# Arduino_PyunPyun.net
KiCad netlist of a schematic drawn in EAGLE
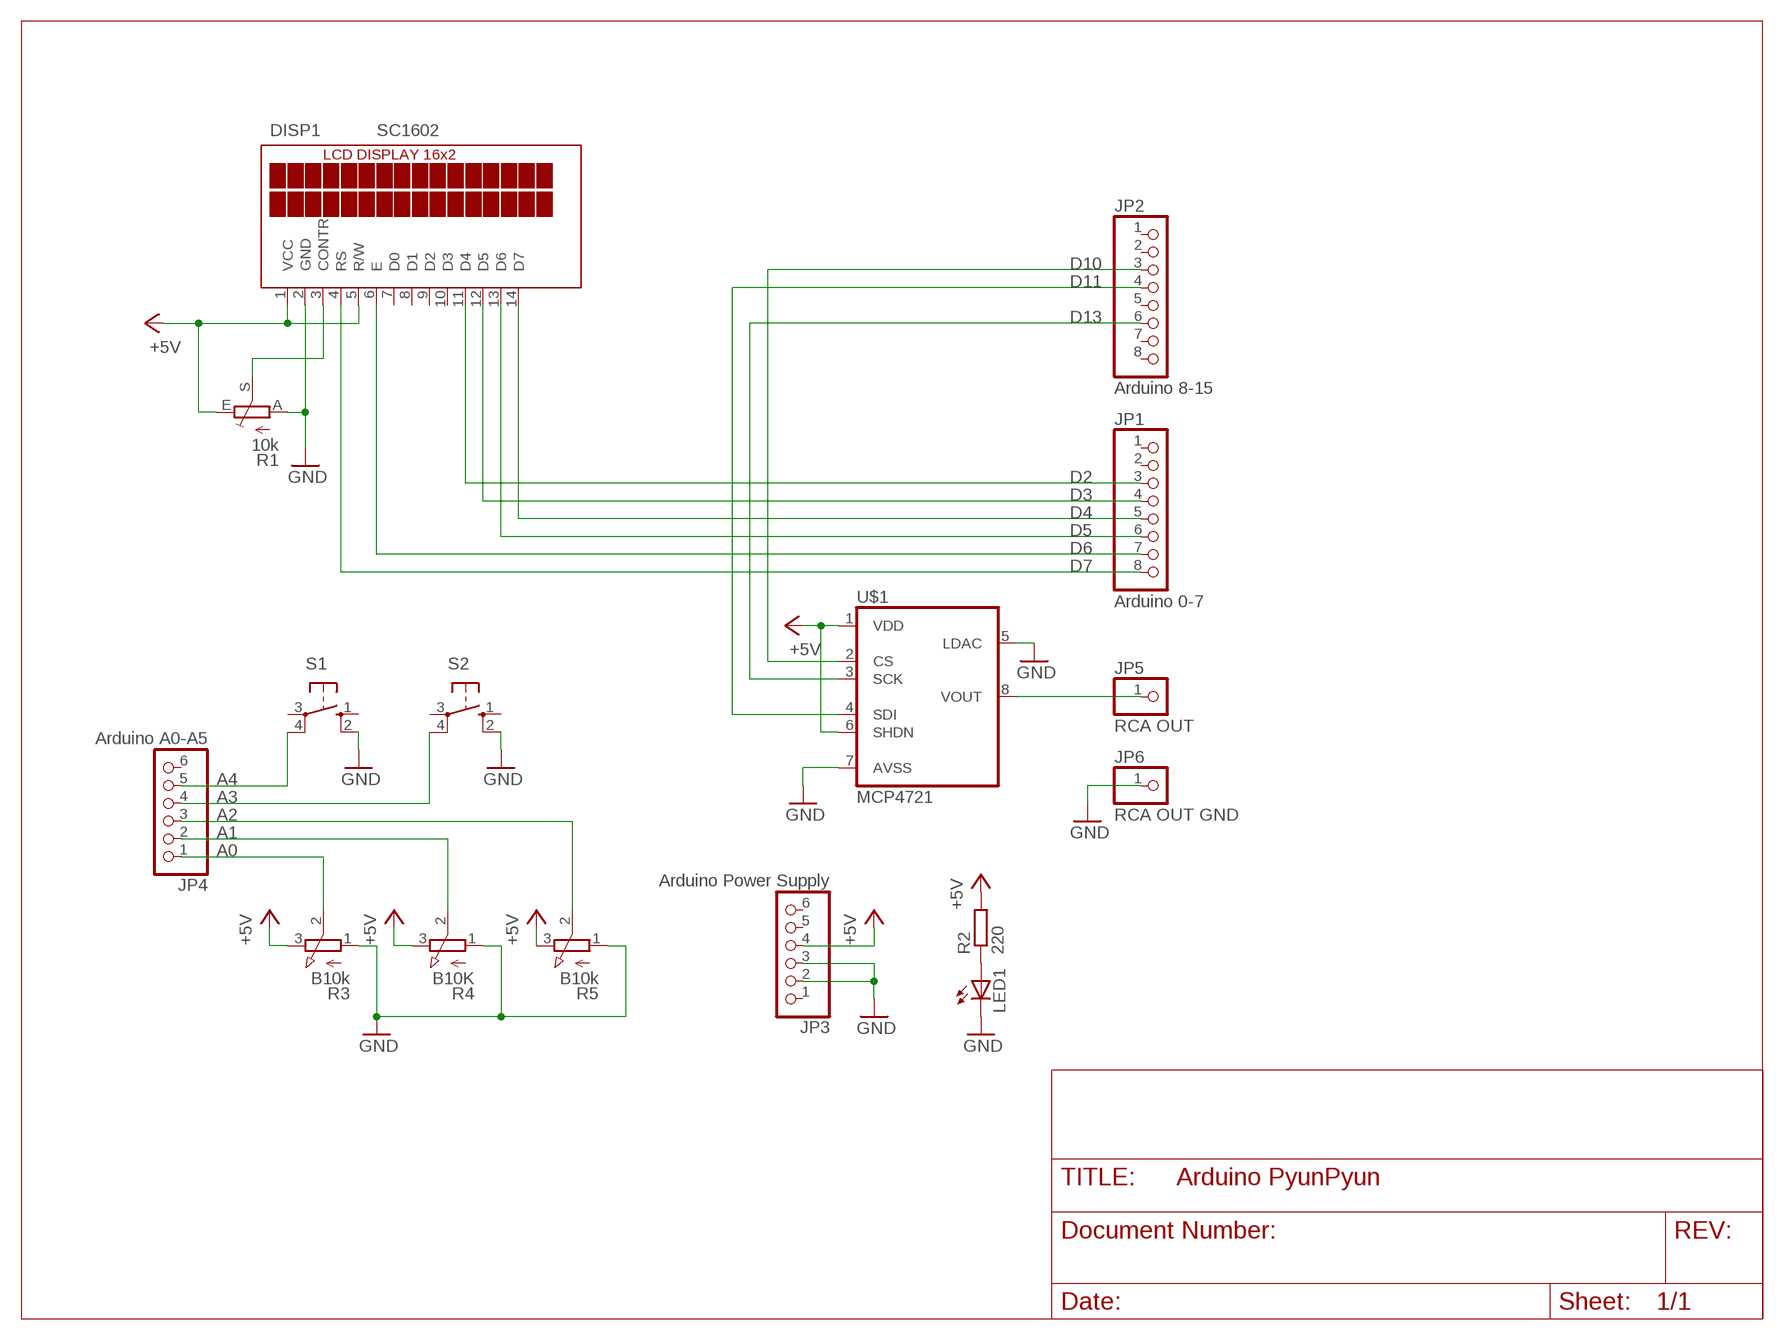
[diagram p0: schematic, sheet 1]

(export (version "E")
  (design (tool "Eeschema 10.0.6"))
  (components
    (comp (ref "DISP1")
      (value "SC1602")
      (footprint "eagle-import:SC1602")
      (libsource (lib "eagle-import") (part "SC1602"))
    )
    (comp (ref "JP1")
      (value "Arduino 0-7")
      (footprint "eagle-import:1X08")
      (libsource (lib "eagle-import") (part "PINHD-1X8"))
    )
    (comp (ref "JP2")
      (value "Arduino 8-15")
      (footprint "eagle-import:1X08")
      (libsource (lib "eagle-import") (part "PINHD-1X8"))
    )
    (comp (ref "JP3")
      (value "Arduino Power Supply")
      (footprint "eagle-import:1X06")
      (libsource (lib "eagle-import") (part "PINHD-1X6"))
    )
    (comp (ref "JP4")
      (value "Arduino A0-A5")
      (footprint "eagle-import:1X06")
      (libsource (lib "eagle-import") (part "PINHD-1X6"))
    )
    (comp (ref "JP5")
      (value "RCA OUT")
      (footprint "eagle-import:1X01")
      (libsource (lib "eagle-import") (part "PINHD-1X1"))
    )
    (comp (ref "JP6")
      (value "RCA OUT GND")
      (footprint "eagle-import:1X01")
      (libsource (lib "eagle-import") (part "PINHD-1X1"))
    )
    (comp (ref "LED1")
      (value "LED5MM")
      (footprint "eagle-import:LED5MM")
      (libsource (lib "eagle-import") (part "LED5MM"))
    )
    (comp (ref "R1")
      (value "10k")
      (footprint "eagle-import:B25P")
      (libsource (lib "eagle-import") (part "TRIM_EU-B25P"))
    )
    (comp (ref "R2")
      (value "220")
      (footprint "eagle-import:0207_7")
      (libsource (lib "eagle-import") (part "R-EU_0207/7"))
    )
    (comp (ref "R3")
      (value "B10k")
      (footprint "eagle-import:3RP_1610N")
      (libsource (lib "eagle-import") (part "3RP/1610N"))
    )
    (comp (ref "R4")
      (value "B10K")
      (footprint "eagle-import:3RP_1610N")
      (libsource (lib "eagle-import") (part "3RP/1610N"))
    )
    (comp (ref "R5")
      (value "B10k")
      (footprint "eagle-import:3RP_1610N")
      (libsource (lib "eagle-import") (part "3RP/1610N"))
    )
    (comp (ref "S1")
      (value "40-XX")
      (footprint "eagle-import:B3F-40XX")
      (fields (field (name "MF") "OMRON COMPONENTS USA") (field (name "MPN") "B3F-4000"))
      (libsource (lib "eagle-import") (part "40-XX"))
    )
    (comp (ref "S2")
      (value "40-XX")
      (footprint "eagle-import:B3F-40XX")
      (fields (field (name "MF") "OMRON COMPONENTS USA") (field (name "MPN") "B3F-4000"))
      (libsource (lib "eagle-import") (part "40-XX"))
    )
    (comp (ref "U$1")
      (value "MCP4721")
      (footprint "eagle-import:MCP4721")
      (libsource (lib "eagle-import") (part "MCP4721"))
    )
  )
  (nets
    (net (code "1") (name "+5V") (class "Default")
      (node (ref "DISP1") (pin "1") (pinfunction "VCC_1") (pintype "power_in"))
      (node (ref "DISP1") (pin "5") (pinfunction "R/W_5") (pintype "input"))
      (node (ref "JP3") (pin "4") (pinfunction "4_4") (pintype "passive"))
      (node (ref "R1") (pin "E") (pinfunction "E_E") (pintype "passive"))
      (node (ref "R2") (pin "2") (pinfunction "2_2") (pintype "passive"))
      (node (ref "R3") (pin "3") (pinfunction "E_3") (pintype "passive"))
      (node (ref "R4") (pin "3") (pinfunction "E_3") (pintype "passive"))
      (node (ref "R5") (pin "3") (pinfunction "E_3") (pintype "passive"))
      (node (ref "U$1") (pin "1") (pinfunction "VDD_1") (pintype "power_in"))
      (node (ref "U$1") (pin "6") (pinfunction "SHDN_6") (pintype "input"))
    )
    (net (code "2") (name "/A0") (class "Default")
      (node (ref "JP4") (pin "1") (pinfunction "1_1") (pintype "passive"))
      (node (ref "R3") (pin "2") (pinfunction "S_2") (pintype "passive"))
    )
    (net (code "3") (name "/A1") (class "Default")
      (node (ref "JP4") (pin "2") (pinfunction "2_2") (pintype "passive"))
      (node (ref "R4") (pin "2") (pinfunction "S_2") (pintype "passive"))
    )
    (net (code "4") (name "/A2") (class "Default")
      (node (ref "JP4") (pin "3") (pinfunction "3_3") (pintype "passive"))
      (node (ref "R5") (pin "2") (pinfunction "S_2") (pintype "passive"))
    )
    (net (code "5") (name "/A3") (class "Default")
      (node (ref "JP4") (pin "4") (pinfunction "4_4") (pintype "passive"))
      (node (ref "S2") (pin "4") (pinfunction "P1_4") (pintype "passive"))
    )
    (net (code "6") (name "/A4") (class "Default")
      (node (ref "JP4") (pin "5") (pinfunction "5_5") (pintype "passive"))
      (node (ref "S1") (pin "4") (pinfunction "P1_4") (pintype "passive"))
    )
    (net (code "7") (name "/D2") (class "Default")
      (node (ref "DISP1") (pin "11") (pinfunction "D4_11") (pintype "input"))
      (node (ref "JP1") (pin "3") (pinfunction "3_3") (pintype "passive"))
    )
    (net (code "8") (name "/D3") (class "Default")
      (node (ref "DISP1") (pin "12") (pinfunction "D5_12") (pintype "input"))
      (node (ref "JP1") (pin "4") (pinfunction "4_4") (pintype "passive"))
    )
    (net (code "9") (name "/D4") (class "Default")
      (node (ref "DISP1") (pin "14") (pinfunction "D7_14") (pintype "input"))
      (node (ref "JP1") (pin "5") (pinfunction "5_5") (pintype "passive"))
    )
    (net (code "10") (name "/D5") (class "Default")
      (node (ref "DISP1") (pin "13") (pinfunction "D6_13") (pintype "input"))
      (node (ref "JP1") (pin "6") (pinfunction "6_6") (pintype "passive"))
    )
    (net (code "11") (name "/D6") (class "Default")
      (node (ref "DISP1") (pin "6") (pinfunction "E_6") (pintype "input"))
      (node (ref "JP1") (pin "7") (pinfunction "7_7") (pintype "passive"))
    )
    (net (code "12") (name "/D7") (class "Default")
      (node (ref "DISP1") (pin "4") (pinfunction "RS_4") (pintype "input"))
      (node (ref "JP1") (pin "8") (pinfunction "8_8") (pintype "passive"))
    )
    (net (code "13") (name "/D10") (class "Default")
      (node (ref "JP2") (pin "3") (pinfunction "3_3") (pintype "passive"))
      (node (ref "U$1") (pin "2") (pinfunction "CS_2") (pintype "input"))
    )
    (net (code "14") (name "/D11") (class "Default")
      (node (ref "JP2") (pin "4") (pinfunction "4_4") (pintype "passive"))
      (node (ref "U$1") (pin "4") (pinfunction "SDI_4") (pintype "input"))
    )
    (net (code "15") (name "/D13") (class "Default")
      (node (ref "JP2") (pin "6") (pinfunction "6_6") (pintype "passive"))
      (node (ref "U$1") (pin "3") (pinfunction "SCK_3") (pintype "output"))
    )
    (net (code "16") (name "GND") (class "Default")
      (node (ref "DISP1") (pin "2") (pinfunction "GND_2") (pintype "power_in"))
      (node (ref "JP3") (pin "2") (pinfunction "2_2") (pintype "passive"))
      (node (ref "JP3") (pin "3") (pinfunction "3_3") (pintype "passive"))
      (node (ref "JP6") (pin "1") (pinfunction "1_1") (pintype "passive"))
      (node (ref "LED1") (pin "K") (pinfunction "C_K") (pintype "passive"))
      (node (ref "R1") (pin "A") (pinfunction "A_A") (pintype "passive"))
      (node (ref "R3") (pin "1") (pinfunction "A_1") (pintype "passive"))
      (node (ref "R4") (pin "1") (pinfunction "A_1") (pintype "passive"))
      (node (ref "R5") (pin "1") (pinfunction "A_1") (pintype "passive"))
      (node (ref "S1") (pin "2") (pinfunction "S1_2") (pintype "passive"))
      (node (ref "S2") (pin "2") (pinfunction "S1_2") (pintype "passive"))
      (node (ref "U$1") (pin "5") (pinfunction "LDAC_5") (pintype "input"))
      (node (ref "U$1") (pin "7") (pinfunction "AVSS_7") (pintype "power_in"))
    )
    (net (code "17") (name "Net-(DISP1-CONTR)") (class "Default")
      (node (ref "DISP1") (pin "3") (pinfunction "CONTR_3") (pintype "input"))
      (node (ref "R1") (pin "S") (pinfunction "S_S") (pintype "passive"))
    )
    (net (code "18") (name "Net-(LED1-PadA)") (class "Default")
      (node (ref "LED1") (pin "A") (pinfunction "A_A") (pintype "passive"))
      (node (ref "R2") (pin "1") (pinfunction "1_1") (pintype "passive"))
    )
    (net (code "19") (name "Net-(U$1-VOUT)") (class "Default")
      (node (ref "JP5") (pin "1") (pinfunction "1_1") (pintype "passive"))
      (node (ref "U$1") (pin "8") (pinfunction "VOUT_8") (pintype "output"))
    )
    (net (code "20") (name "unconnected-(DISP1-D0-Pad7)") (class "Default")
      (node (ref "DISP1") (pin "7") (pinfunction "D0_7") (pintype "input"))
    )
    (net (code "21") (name "unconnected-(DISP1-D1-Pad8)") (class "Default")
      (node (ref "DISP1") (pin "8") (pinfunction "D1_8") (pintype "input"))
    )
    (net (code "22") (name "unconnected-(DISP1-D2-Pad9)") (class "Default")
      (node (ref "DISP1") (pin "9") (pinfunction "D2_9") (pintype "input"))
    )
    (net (code "23") (name "unconnected-(DISP1-D3-Pad10)") (class "Default")
      (node (ref "DISP1") (pin "10") (pinfunction "D3_10") (pintype "input"))
    )
    (net (code "24") (name "unconnected-(JP1-Pad1)") (class "Default")
      (node (ref "JP1") (pin "1") (pinfunction "1_1") (pintype "passive"))
    )
    (net (code "25") (name "unconnected-(JP1-Pad2)") (class "Default")
      (node (ref "JP1") (pin "2") (pinfunction "2_2") (pintype "passive"))
    )
    (net (code "26") (name "unconnected-(JP2-Pad1)") (class "Default")
      (node (ref "JP2") (pin "1") (pinfunction "1_1") (pintype "passive"))
    )
    (net (code "27") (name "unconnected-(JP2-Pad2)") (class "Default")
      (node (ref "JP2") (pin "2") (pinfunction "2_2") (pintype "passive"))
    )
    (net (code "28") (name "unconnected-(JP2-Pad5)") (class "Default")
      (node (ref "JP2") (pin "5") (pinfunction "5_5") (pintype "passive"))
    )
    (net (code "29") (name "unconnected-(JP2-Pad7)") (class "Default")
      (node (ref "JP2") (pin "7") (pinfunction "7_7") (pintype "passive"))
    )
    (net (code "30") (name "unconnected-(JP2-Pad8)") (class "Default")
      (node (ref "JP2") (pin "8") (pinfunction "8_8") (pintype "passive"))
    )
    (net (code "31") (name "unconnected-(JP3-Pad1)") (class "Default")
      (node (ref "JP3") (pin "1") (pinfunction "1_1") (pintype "passive"))
    )
    (net (code "32") (name "unconnected-(JP3-Pad5)") (class "Default")
      (node (ref "JP3") (pin "5") (pinfunction "5_5") (pintype "passive"))
    )
    (net (code "33") (name "unconnected-(JP3-Pad6)") (class "Default")
      (node (ref "JP3") (pin "6") (pinfunction "6_6") (pintype "passive"))
    )
    (net (code "34") (name "unconnected-(JP4-Pad6)") (class "Default")
      (node (ref "JP4") (pin "6") (pinfunction "6_6") (pintype "passive"))
    )
    (net (code "35") (name "unconnected-(S1-P-Pad3)") (class "Default")
      (node (ref "S1") (pin "3") (pinfunction "P_3") (pintype "passive"))
    )
    (net (code "36") (name "unconnected-(S1-S-Pad1)") (class "Default")
      (node (ref "S1") (pin "1") (pinfunction "S_1") (pintype "passive"))
    )
    (net (code "37") (name "unconnected-(S2-P-Pad3)") (class "Default")
      (node (ref "S2") (pin "3") (pinfunction "P_3") (pintype "passive"))
    )
    (net (code "38") (name "unconnected-(S2-S-Pad1)") (class "Default")
      (node (ref "S2") (pin "1") (pinfunction "S_1") (pintype "passive"))
    )
  )
)
